# magnetorquer_extension_board_f1.net
KiCad netlist of a schematic drawn in EAGLE
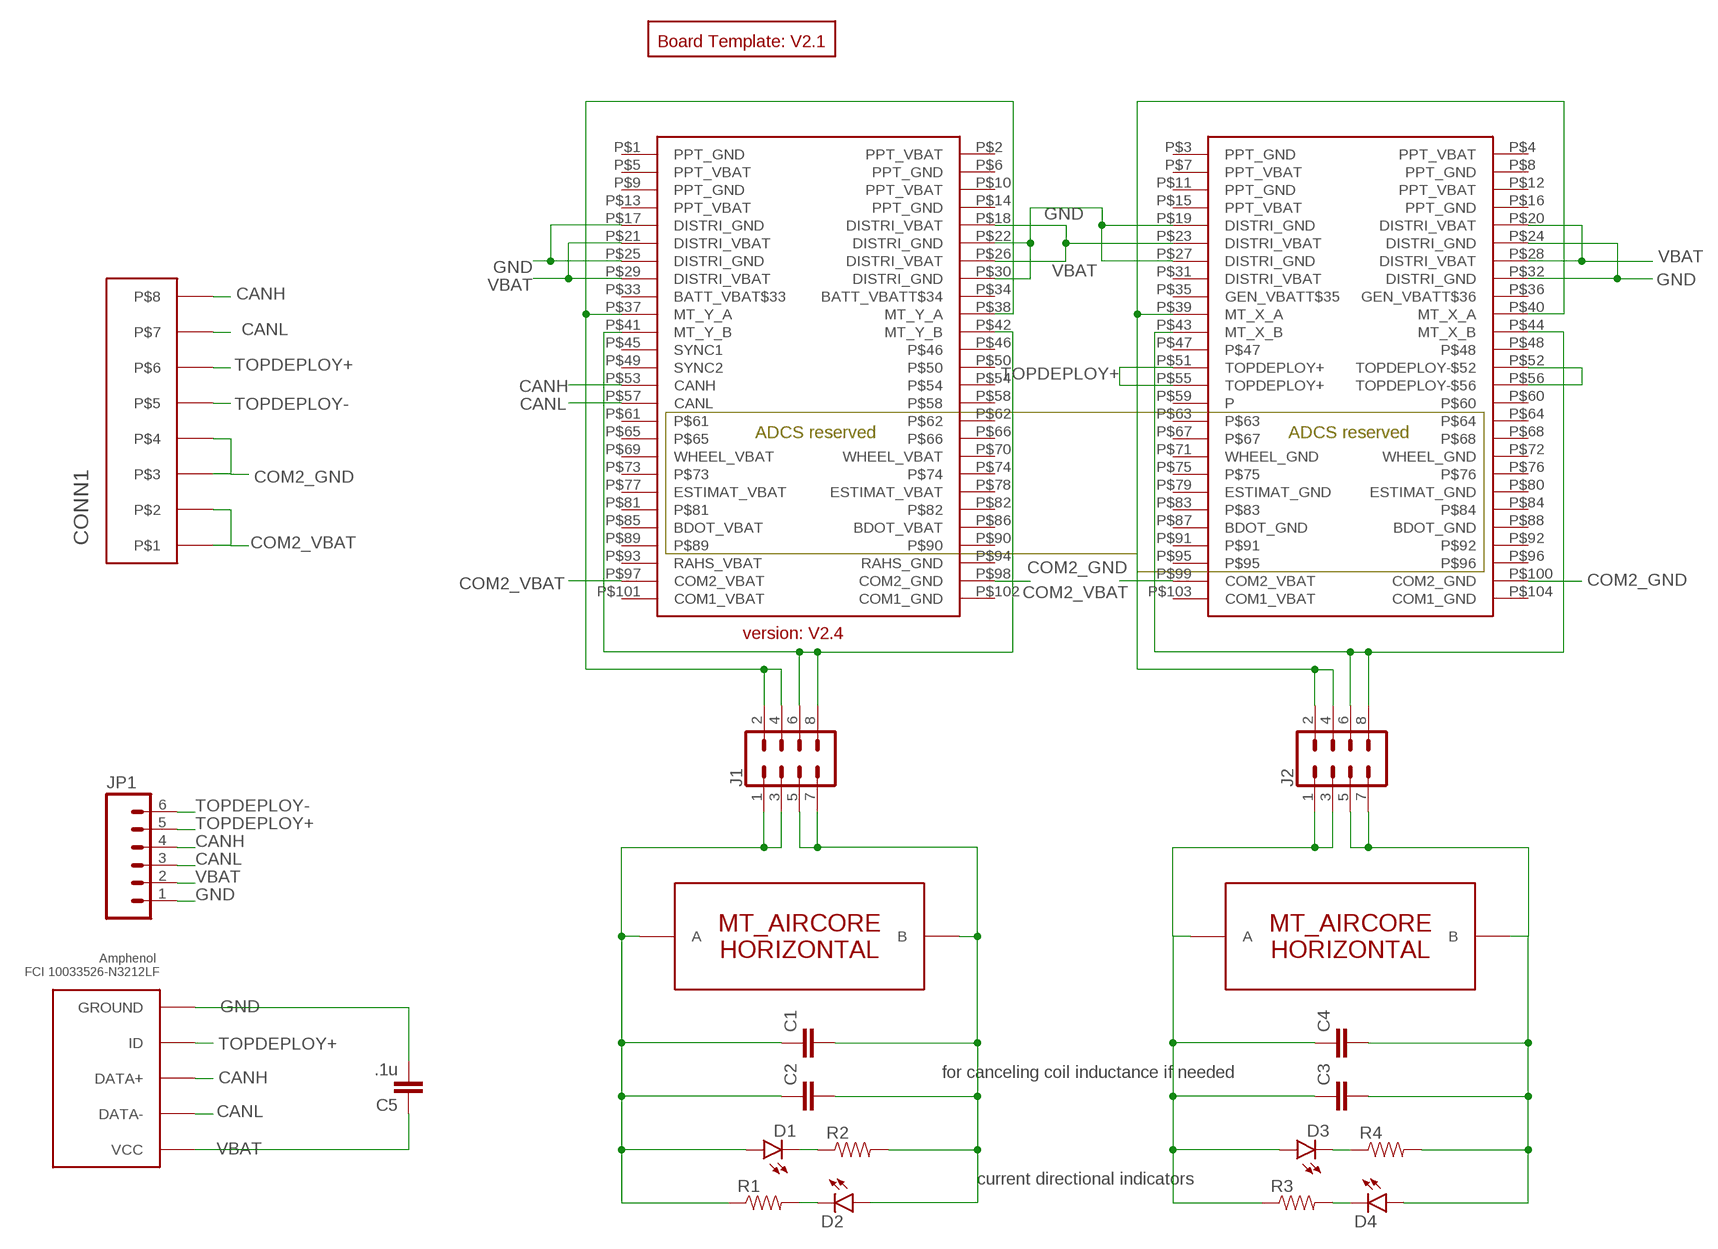
[diagram p0: schematic, sheet 1]

(export (version "E")
  (design (tool "Eeschema 10.0.6"))
  (components
    (comp (ref "C1")
      (value "CAPACITOR0805")
      (footprint "eagle-import:0805")
      (libsource (lib "eagle-import") (part "CAPACITOR0805"))
    )
    (comp (ref "C2")
      (value "CAPACITOR1210")
      (footprint "eagle-import:1210")
      (libsource (lib "eagle-import") (part "CAPACITOR1210"))
    )
    (comp (ref "C3")
      (value "CAPACITOR1210")
      (footprint "eagle-import:1210")
      (libsource (lib "eagle-import") (part "CAPACITOR1210"))
    )
    (comp (ref "C4")
      (value "CAPACITOR0805")
      (footprint "eagle-import:0805")
      (libsource (lib "eagle-import") (part "CAPACITOR0805"))
    )
    (comp (ref "C5")
      (value ".1u")
      (footprint "eagle-import:0805")
      (libsource (lib "eagle-import") (part "CAPACITOR0805"))
    )
    (comp (ref "CONN1")
      (value "PICOLOCK_8PICOLOCK_8")
      (footprint "eagle-import:PICOLOCK_8")
      (libsource (lib "eagle-import") (part "PICOLOCK_8PICOLOCK_8"))
    )
    (comp (ref "D1")
      (value "LED")
      (footprint "eagle-import:LED-1206")
      (libsource (lib "eagle-import") (part "LED"))
    )
    (comp (ref "D2")
      (value "LED")
      (footprint "eagle-import:LED-1206")
      (libsource (lib "eagle-import") (part "LED"))
    )
    (comp (ref "D3")
      (value "LED")
      (footprint "eagle-import:LED-1206")
      (libsource (lib "eagle-import") (part "LED"))
    )
    (comp (ref "D4")
      (value "LED")
      (footprint "eagle-import:LED-1206")
      (libsource (lib "eagle-import") (part "LED"))
    )
    (comp (ref "J1")
      (value "CONN_04X2")
      (footprint "eagle-import:2X4")
      (libsource (lib "eagle-import") (part "CONN_04X2"))
    )
    (comp (ref "J2")
      (value "CONN_04X2")
      (footprint "eagle-import:2X4")
      (libsource (lib "eagle-import") (part "CONN_04X2"))
    )
    (comp (ref "JP1")
      (value "M06LOCK")
      (footprint "eagle-import:1X06_LOCK")
      (libsource (lib "eagle-import") (part "M06LOCK"))
    )
    (comp (ref "MT_X")
      (value "MT_AIRCORE_HORIZONTAL")
      (footprint "eagle-import:MT_AIRCORE_HORIZONTAL")
      (libsource (lib "eagle-import") (part "MT_AIRCORE_HORIZONTAL"))
    )
    (comp (ref "MT_Y")
      (value "MT_AIRCORE_HORIZONTAL")
      (footprint "eagle-import:MT_AIRCORE_HORIZONTAL")
      (libsource (lib "eagle-import") (part "MT_AIRCORE_HORIZONTAL"))
    )
    (comp (ref "R1")
      (value "RESISTOR0805")
      (footprint "eagle-import:0805")
      (libsource (lib "eagle-import") (part "RESISTOR0805"))
    )
    (comp (ref "R2")
      (value "RESISTOR0805")
      (footprint "eagle-import:0805")
      (libsource (lib "eagle-import") (part "RESISTOR0805"))
    )
    (comp (ref "R3")
      (value "RESISTOR0805")
      (footprint "eagle-import:0805")
      (libsource (lib "eagle-import") (part "RESISTOR0805"))
    )
    (comp (ref "R4")
      (value "RESISTOR0805")
      (footprint "eagle-import:0805")
      (libsource (lib "eagle-import") (part "RESISTOR0805"))
    )
    (comp (ref "U$1")
      (value "PC104_CONNECTOR")
      (footprint "eagle-import:PC104_CONNECTOR")
      (libsource (lib "eagle-import") (part "PC104_CONNECTOR"))
    )
    (comp (ref "U$2")
      (value "BOARD_TEMPLATESERCURED")
      (footprint "eagle-import:BOARD_TEMPLATE_SECURED")
      (libsource (lib "eagle-import") (part "BOARD_TEMPLATESERCURED"))
    )
    (comp (ref "U$3")
      (value "USB_MINI-B_AMPHENOL")
      (footprint "eagle-import:USB_MINI_B")
      (libsource (lib "eagle-import") (part "USB_MINI-B_AMPHENOL"))
    )
  )
  (nets
    (net (code "1") (name "/CANH") (class "Default")
      (node (ref "CONN1") (pin "P$8") (pinfunction "P$8_P$8") (pintype "bidirectional"))
      (node (ref "JP1") (pin "4") (pinfunction "4_4") (pintype "passive"))
      (node (ref "U$1") (pin "P$53") (pinfunction "CANH_P$53") (pintype "bidirectional"))
      (node (ref "U$3") (pin "DATA+") (pinfunction "DATA+_DATA+") (pintype "bidirectional"))
    )
    (net (code "2") (name "/CANL") (class "Default")
      (node (ref "CONN1") (pin "P$7") (pinfunction "P$7_P$7") (pintype "bidirectional"))
      (node (ref "JP1") (pin "3") (pinfunction "3_3") (pintype "passive"))
      (node (ref "U$1") (pin "P$57") (pinfunction "CANL_P$57") (pintype "bidirectional"))
      (node (ref "U$3") (pin "DATA-") (pinfunction "DATA-_DATA-") (pintype "bidirectional"))
    )
    (net (code "3") (name "/COM2_GND") (class "Default")
      (node (ref "CONN1") (pin "P$3") (pinfunction "P$3_P$3") (pintype "bidirectional"))
      (node (ref "CONN1") (pin "P$4") (pinfunction "P$4_P$4") (pintype "bidirectional"))
      (node (ref "U$1") (pin "P$100") (pinfunction "COM2_GND_P$100") (pintype "bidirectional"))
      (node (ref "U$1") (pin "P$98") (pinfunction "COM2_GND_P$98") (pintype "bidirectional"))
    )
    (net (code "4") (name "/COM2_VBAT") (class "Default")
      (node (ref "CONN1") (pin "P$1") (pinfunction "P$1_P$1") (pintype "bidirectional"))
      (node (ref "CONN1") (pin "P$2") (pinfunction "P$2_P$2") (pintype "bidirectional"))
      (node (ref "U$1") (pin "P$97") (pinfunction "COM2_VBAT_P$97") (pintype "bidirectional"))
      (node (ref "U$1") (pin "P$99") (pinfunction "COM2_VBAT_P$99") (pintype "bidirectional"))
    )
    (net (code "5") (name "/GND") (class "Default")
      (node (ref "C5") (pin "2") (pinfunction "2_2") (pintype "passive"))
      (node (ref "JP1") (pin "1") (pinfunction "1_1") (pintype "passive"))
      (node (ref "U$1") (pin "P$17") (pinfunction "DISTRI_GND_P$17") (pintype "bidirectional"))
      (node (ref "U$1") (pin "P$19") (pinfunction "DISTRI_GND_P$19") (pintype "bidirectional"))
      (node (ref "U$1") (pin "P$22") (pinfunction "DISTRI_GND_P$22") (pintype "bidirectional"))
      (node (ref "U$1") (pin "P$24") (pinfunction "DISTRI_GND_P$24") (pintype "bidirectional"))
      (node (ref "U$1") (pin "P$25") (pinfunction "DISTRI_GND_P$25") (pintype "bidirectional"))
      (node (ref "U$1") (pin "P$27") (pinfunction "DISTRI_GND_P$27") (pintype "bidirectional"))
      (node (ref "U$1") (pin "P$30") (pinfunction "DISTRI_GND_P$30") (pintype "bidirectional"))
      (node (ref "U$1") (pin "P$32") (pinfunction "DISTRI_GND_P$32") (pintype "bidirectional"))
      (node (ref "U$3") (pin "GND1") (pinfunction "GROUND_GND1") (pintype "bidirectional"))
      (node (ref "U$3") (pin "GND2") (pinfunction "GROUND_GND2") (pintype "bidirectional"))
      (node (ref "U$3") (pin "GND3") (pinfunction "GROUND_GND3") (pintype "bidirectional"))
      (node (ref "U$3") (pin "GND4") (pinfunction "GROUND_GND4") (pintype "bidirectional"))
      (node (ref "U$3") (pin "GROUND") (pinfunction "GROUND_GROUND") (pintype "bidirectional"))
    )
    (net (code "6") (name "/TOPDEPLOY+") (class "Default")
      (node (ref "CONN1") (pin "P$6") (pinfunction "P$6_P$6") (pintype "bidirectional"))
      (node (ref "JP1") (pin "5") (pinfunction "5_5") (pintype "passive"))
      (node (ref "U$1") (pin "P$51") (pinfunction "TOPDEPLOY+_P$51") (pintype "bidirectional"))
      (node (ref "U$1") (pin "P$55") (pinfunction "TOPDEPLOY+_P$55") (pintype "bidirectional"))
      (node (ref "U$3") (pin "ID") (pinfunction "ID_ID") (pintype "bidirectional"))
    )
    (net (code "7") (name "/TOPDEPLOY-") (class "Default")
      (node (ref "CONN1") (pin "P$5") (pinfunction "P$5_P$5") (pintype "bidirectional"))
      (node (ref "JP1") (pin "6") (pinfunction "6_6") (pintype "passive"))
      (node (ref "U$1") (pin "P$52") (pinfunction "TOPDEPLOY-$52_P$52") (pintype "bidirectional"))
      (node (ref "U$1") (pin "P$56") (pinfunction "TOPDEPLOY-$56_P$56") (pintype "bidirectional"))
    )
    (net (code "8") (name "/VBAT") (class "Default")
      (node (ref "C5") (pin "1") (pinfunction "1_1") (pintype "passive"))
      (node (ref "JP1") (pin "2") (pinfunction "2_2") (pintype "passive"))
      (node (ref "U$1") (pin "P$18") (pinfunction "DISTRI_VBAT_P$18") (pintype "bidirectional"))
      (node (ref "U$1") (pin "P$20") (pinfunction "DISTRI_VBAT_P$20") (pintype "bidirectional"))
      (node (ref "U$1") (pin "P$21") (pinfunction "DISTRI_VBAT_P$21") (pintype "bidirectional"))
      (node (ref "U$1") (pin "P$23") (pinfunction "DISTRI_VBAT_P$23") (pintype "bidirectional"))
      (node (ref "U$1") (pin "P$26") (pinfunction "DISTRI_VBAT_P$26") (pintype "bidirectional"))
      (node (ref "U$1") (pin "P$28") (pinfunction "DISTRI_VBAT_P$28") (pintype "bidirectional"))
      (node (ref "U$1") (pin "P$29") (pinfunction "DISTRI_VBAT_P$29") (pintype "bidirectional"))
      (node (ref "U$3") (pin "VCC") (pinfunction "VCC_VCC") (pintype "bidirectional"))
    )
    (net (code "9") (name "Net-(C1-Pad1)") (class "Default")
      (node (ref "C1") (pin "1") (pinfunction "1_1") (pintype "passive"))
      (node (ref "C2") (pin "1") (pinfunction "1_1") (pintype "passive"))
      (node (ref "D1") (pin "A") (pinfunction "A_A") (pintype "passive"))
      (node (ref "J1") (pin "1") (pinfunction "1_1") (pintype "passive"))
      (node (ref "J1") (pin "3") (pinfunction "3_3") (pintype "passive"))
      (node (ref "MT_X") (pin "A") (pinfunction "A_A") (pintype "bidirectional"))
      (node (ref "R1") (pin "1") (pinfunction "1_1") (pintype "passive"))
    )
    (net (code "10") (name "Net-(C1-Pad2)") (class "Default")
      (node (ref "C1") (pin "2") (pinfunction "2_2") (pintype "passive"))
      (node (ref "C2") (pin "2") (pinfunction "2_2") (pintype "passive"))
      (node (ref "D2") (pin "A") (pinfunction "A_A") (pintype "passive"))
      (node (ref "J1") (pin "5") (pinfunction "5_5") (pintype "passive"))
      (node (ref "J1") (pin "7") (pinfunction "7_7") (pintype "passive"))
      (node (ref "MT_X") (pin "B") (pinfunction "B_B") (pintype "bidirectional"))
      (node (ref "R2") (pin "2") (pinfunction "2_2") (pintype "passive"))
    )
    (net (code "11") (name "Net-(C3-Pad1)") (class "Default")
      (node (ref "C3") (pin "1") (pinfunction "1_1") (pintype "passive"))
      (node (ref "C4") (pin "1") (pinfunction "1_1") (pintype "passive"))
      (node (ref "D3") (pin "A") (pinfunction "A_A") (pintype "passive"))
      (node (ref "J2") (pin "1") (pinfunction "1_1") (pintype "passive"))
      (node (ref "J2") (pin "3") (pinfunction "3_3") (pintype "passive"))
      (node (ref "MT_Y") (pin "A") (pinfunction "A_A") (pintype "bidirectional"))
      (node (ref "R3") (pin "1") (pinfunction "1_1") (pintype "passive"))
    )
    (net (code "12") (name "Net-(C3-Pad2)") (class "Default")
      (node (ref "C3") (pin "2") (pinfunction "2_2") (pintype "passive"))
      (node (ref "C4") (pin "2") (pinfunction "2_2") (pintype "passive"))
      (node (ref "D4") (pin "A") (pinfunction "A_A") (pintype "passive"))
      (node (ref "J2") (pin "5") (pinfunction "5_5") (pintype "passive"))
      (node (ref "J2") (pin "7") (pinfunction "7_7") (pintype "passive"))
      (node (ref "MT_Y") (pin "B") (pinfunction "B_B") (pintype "bidirectional"))
      (node (ref "R4") (pin "2") (pinfunction "2_2") (pintype "passive"))
    )
    (net (code "13") (name "Net-(D1-PadC)") (class "Default")
      (node (ref "D1") (pin "C") (pinfunction "C_C") (pintype "passive"))
      (node (ref "R2") (pin "1") (pinfunction "1_1") (pintype "passive"))
    )
    (net (code "14") (name "Net-(D2-PadC)") (class "Default")
      (node (ref "D2") (pin "C") (pinfunction "C_C") (pintype "passive"))
      (node (ref "R1") (pin "2") (pinfunction "2_2") (pintype "passive"))
    )
    (net (code "15") (name "Net-(D3-PadC)") (class "Default")
      (node (ref "D3") (pin "C") (pinfunction "C_C") (pintype "passive"))
      (node (ref "R4") (pin "1") (pinfunction "1_1") (pintype "passive"))
    )
    (net (code "16") (name "Net-(D4-PadC)") (class "Default")
      (node (ref "D4") (pin "C") (pinfunction "C_C") (pintype "passive"))
      (node (ref "R3") (pin "2") (pinfunction "2_2") (pintype "passive"))
    )
    (net (code "17") (name "Net-(J1-Pad2)") (class "Default")
      (node (ref "J1") (pin "2") (pinfunction "2_2") (pintype "passive"))
      (node (ref "J1") (pin "4") (pinfunction "4_4") (pintype "passive"))
      (node (ref "U$1") (pin "P$37") (pinfunction "MT_Y_A_P$37") (pintype "bidirectional"))
      (node (ref "U$1") (pin "P$38") (pinfunction "MT_Y_A_P$38") (pintype "bidirectional"))
    )
    (net (code "18") (name "Net-(J1-Pad6)") (class "Default")
      (node (ref "J1") (pin "6") (pinfunction "6_6") (pintype "passive"))
      (node (ref "J1") (pin "8") (pinfunction "8_8") (pintype "passive"))
      (node (ref "U$1") (pin "P$41") (pinfunction "MT_Y_B_P$41") (pintype "bidirectional"))
      (node (ref "U$1") (pin "P$42") (pinfunction "MT_Y_B_P$42") (pintype "bidirectional"))
    )
    (net (code "19") (name "Net-(J2-Pad2)") (class "Default")
      (node (ref "J2") (pin "2") (pinfunction "2_2") (pintype "passive"))
      (node (ref "J2") (pin "4") (pinfunction "4_4") (pintype "passive"))
      (node (ref "U$1") (pin "P$39") (pinfunction "MT_X_A_P$39") (pintype "bidirectional"))
      (node (ref "U$1") (pin "P$40") (pinfunction "MT_X_A_P$40") (pintype "bidirectional"))
    )
    (net (code "20") (name "Net-(J2-Pad6)") (class "Default")
      (node (ref "J2") (pin "6") (pinfunction "6_6") (pintype "passive"))
      (node (ref "J2") (pin "8") (pinfunction "8_8") (pintype "passive"))
      (node (ref "U$1") (pin "P$43") (pinfunction "MT_X_B_P$43") (pintype "bidirectional"))
      (node (ref "U$1") (pin "P$44") (pinfunction "MT_X_B_P$44") (pintype "bidirectional"))
    )
    (net (code "21") (name "unconnected-(U$1-BATT_VBAT$33-PadP$33)") (class "Default")
      (node (ref "U$1") (pin "P$33") (pinfunction "BATT_VBAT$33_P$33") (pintype "bidirectional"))
    )
    (net (code "22") (name "unconnected-(U$1-BATT_VBATT$34-PadP$34)") (class "Default")
      (node (ref "U$1") (pin "P$34") (pinfunction "BATT_VBATT$34_P$34") (pintype "bidirectional"))
    )
    (net (code "23") (name "unconnected-(U$1-BDOT_GND-PadP$87)") (class "Default")
      (node (ref "U$1") (pin "P$87") (pinfunction "BDOT_GND_P$87") (pintype "bidirectional"))
    )
    (net (code "24") (name "unconnected-(U$1-BDOT_GND-PadP$88)") (class "Default")
      (node (ref "U$1") (pin "P$88") (pinfunction "BDOT_GND_P$88") (pintype "bidirectional"))
    )
    (net (code "25") (name "unconnected-(U$1-BDOT_VBAT-PadP$85)") (class "Default")
      (node (ref "U$1") (pin "P$85") (pinfunction "BDOT_VBAT_P$85") (pintype "bidirectional"))
    )
    (net (code "26") (name "unconnected-(U$1-BDOT_VBAT-PadP$86)") (class "Default")
      (node (ref "U$1") (pin "P$86") (pinfunction "BDOT_VBAT_P$86") (pintype "bidirectional"))
    )
    (net (code "27") (name "unconnected-(U$1-COM1_GND-PadP$102)") (class "Default")
      (node (ref "U$1") (pin "P$102") (pinfunction "COM1_GND_P$102") (pintype "bidirectional"))
    )
    (net (code "28") (name "unconnected-(U$1-COM1_GND-PadP$104)") (class "Default")
      (node (ref "U$1") (pin "P$104") (pinfunction "COM1_GND_P$104") (pintype "bidirectional"))
    )
    (net (code "29") (name "unconnected-(U$1-COM1_VBAT-PadP$101)") (class "Default")
      (node (ref "U$1") (pin "P$101") (pinfunction "COM1_VBAT_P$101") (pintype "bidirectional"))
    )
    (net (code "30") (name "unconnected-(U$1-COM1_VBAT-PadP$103)") (class "Default")
      (node (ref "U$1") (pin "P$103") (pinfunction "COM1_VBAT_P$103") (pintype "bidirectional"))
    )
    (net (code "31") (name "unconnected-(U$1-DISTRI_VBAT-PadP$31)") (class "Default")
      (node (ref "U$1") (pin "P$31") (pinfunction "DISTRI_VBAT_P$31") (pintype "bidirectional"))
    )
    (net (code "32") (name "unconnected-(U$1-ESTIMAT_GND-PadP$79)") (class "Default")
      (node (ref "U$1") (pin "P$79") (pinfunction "ESTIMAT_GND_P$79") (pintype "bidirectional"))
    )
    (net (code "33") (name "unconnected-(U$1-ESTIMAT_GND-PadP$80)") (class "Default")
      (node (ref "U$1") (pin "P$80") (pinfunction "ESTIMAT_GND_P$80") (pintype "bidirectional"))
    )
    (net (code "34") (name "unconnected-(U$1-ESTIMAT_VBAT-PadP$77)") (class "Default")
      (node (ref "U$1") (pin "P$77") (pinfunction "ESTIMAT_VBAT_P$77") (pintype "bidirectional"))
    )
    (net (code "35") (name "unconnected-(U$1-ESTIMAT_VBAT-PadP$78)") (class "Default")
      (node (ref "U$1") (pin "P$78") (pinfunction "ESTIMAT_VBAT_P$78") (pintype "bidirectional"))
    )
    (net (code "36") (name "unconnected-(U$1-GEN_VBATT$35-PadP$35)") (class "Default")
      (node (ref "U$1") (pin "P$35") (pinfunction "GEN_VBATT$35_P$35") (pintype "bidirectional"))
    )
    (net (code "37") (name "unconnected-(U$1-GEN_VBATT$36-PadP$36)") (class "Default")
      (node (ref "U$1") (pin "P$36") (pinfunction "GEN_VBATT$36_P$36") (pintype "bidirectional"))
    )
    (net (code "38") (name "unconnected-(U$1-P-PadP$59)") (class "Default")
      (node (ref "U$1") (pin "P$59") (pinfunction "P_P$59") (pintype "bidirectional"))
    )
    (net (code "39") (name "unconnected-(U$1-PPT_GND-PadP$1)") (class "Default")
      (node (ref "U$1") (pin "P$1") (pinfunction "PPT_GND_P$1") (pintype "bidirectional"))
    )
    (net (code "40") (name "unconnected-(U$1-PPT_GND-PadP$3)") (class "Default")
      (node (ref "U$1") (pin "P$3") (pinfunction "PPT_GND_P$3") (pintype "bidirectional"))
    )
    (net (code "41") (name "unconnected-(U$1-PPT_GND-PadP$6)") (class "Default")
      (node (ref "U$1") (pin "P$6") (pinfunction "PPT_GND_P$6") (pintype "bidirectional"))
    )
    (net (code "42") (name "unconnected-(U$1-PPT_GND-PadP$8)") (class "Default")
      (node (ref "U$1") (pin "P$8") (pinfunction "PPT_GND_P$8") (pintype "bidirectional"))
    )
    (net (code "43") (name "unconnected-(U$1-PPT_GND-PadP$9)") (class "Default")
      (node (ref "U$1") (pin "P$9") (pinfunction "PPT_GND_P$9") (pintype "bidirectional"))
    )
    (net (code "44") (name "unconnected-(U$1-PPT_GND-PadP$11)") (class "Default")
      (node (ref "U$1") (pin "P$11") (pinfunction "PPT_GND_P$11") (pintype "bidirectional"))
    )
    (net (code "45") (name "unconnected-(U$1-PPT_GND-PadP$14)") (class "Default")
      (node (ref "U$1") (pin "P$14") (pinfunction "PPT_GND_P$14") (pintype "bidirectional"))
    )
    (net (code "46") (name "unconnected-(U$1-PPT_GND-PadP$16)") (class "Default")
      (node (ref "U$1") (pin "P$16") (pinfunction "PPT_GND_P$16") (pintype "bidirectional"))
    )
    (net (code "47") (name "unconnected-(U$1-PPT_VBAT-PadP$2)") (class "Default")
      (node (ref "U$1") (pin "P$2") (pinfunction "PPT_VBAT_P$2") (pintype "bidirectional"))
    )
    (net (code "48") (name "unconnected-(U$1-PPT_VBAT-PadP$4)") (class "Default")
      (node (ref "U$1") (pin "P$4") (pinfunction "PPT_VBAT_P$4") (pintype "bidirectional"))
    )
    (net (code "49") (name "unconnected-(U$1-PPT_VBAT-PadP$5)") (class "Default")
      (node (ref "U$1") (pin "P$5") (pinfunction "PPT_VBAT_P$5") (pintype "bidirectional"))
    )
    (net (code "50") (name "unconnected-(U$1-PPT_VBAT-PadP$7)") (class "Default")
      (node (ref "U$1") (pin "P$7") (pinfunction "PPT_VBAT_P$7") (pintype "bidirectional"))
    )
    (net (code "51") (name "unconnected-(U$1-PPT_VBAT-PadP$10)") (class "Default")
      (node (ref "U$1") (pin "P$10") (pinfunction "PPT_VBAT_P$10") (pintype "bidirectional"))
    )
    (net (code "52") (name "unconnected-(U$1-PPT_VBAT-PadP$12)") (class "Default")
      (node (ref "U$1") (pin "P$12") (pinfunction "PPT_VBAT_P$12") (pintype "bidirectional"))
    )
    (net (code "53") (name "unconnected-(U$1-PPT_VBAT-PadP$13)") (class "Default")
      (node (ref "U$1") (pin "P$13") (pinfunction "PPT_VBAT_P$13") (pintype "bidirectional"))
    )
    (net (code "54") (name "unconnected-(U$1-PPT_VBAT-PadP$15)") (class "Default")
      (node (ref "U$1") (pin "P$15") (pinfunction "PPT_VBAT_P$15") (pintype "bidirectional"))
    )
    (net (code "55") (name "unconnected-(U$1-PadP$46)") (class "Default")
      (node (ref "U$1") (pin "P$46") (pinfunction "P$46_P$46") (pintype "bidirectional"))
    )
    (net (code "56") (name "unconnected-(U$1-PadP$47)") (class "Default")
      (node (ref "U$1") (pin "P$47") (pinfunction "P$47_P$47") (pintype "bidirectional"))
    )
    (net (code "57") (name "unconnected-(U$1-PadP$48)") (class "Default")
      (node (ref "U$1") (pin "P$48") (pinfunction "P$48_P$48") (pintype "bidirectional"))
    )
    (net (code "58") (name "unconnected-(U$1-PadP$50)") (class "Default")
      (node (ref "U$1") (pin "P$50") (pinfunction "P$50_P$50") (pintype "bidirectional"))
    )
    (net (code "59") (name "unconnected-(U$1-PadP$54)") (class "Default")
      (node (ref "U$1") (pin "P$54") (pinfunction "P$54_P$54") (pintype "bidirectional"))
    )
    (net (code "60") (name "unconnected-(U$1-PadP$58)") (class "Default")
      (node (ref "U$1") (pin "P$58") (pinfunction "P$58_P$58") (pintype "bidirectional"))
    )
    (net (code "61") (name "unconnected-(U$1-PadP$60)") (class "Default")
      (node (ref "U$1") (pin "P$60") (pinfunction "P$60_P$60") (pintype "bidirectional"))
    )
    (net (code "62") (name "unconnected-(U$1-PadP$61)") (class "Default")
      (node (ref "U$1") (pin "P$61") (pinfunction "P$61_P$61") (pintype "bidirectional"))
    )
    (net (code "63") (name "unconnected-(U$1-PadP$62)") (class "Default")
      (node (ref "U$1") (pin "P$62") (pinfunction "P$62_P$62") (pintype "bidirectional"))
    )
    (net (code "64") (name "unconnected-(U$1-PadP$63)") (class "Default")
      (node (ref "U$1") (pin "P$63") (pinfunction "P$63_P$63") (pintype "bidirectional"))
    )
    (net (code "65") (name "unconnected-(U$1-PadP$64)") (class "Default")
      (node (ref "U$1") (pin "P$64") (pinfunction "P$64_P$64") (pintype "bidirectional"))
    )
    (net (code "66") (name "unconnected-(U$1-PadP$65)") (class "Default")
      (node (ref "U$1") (pin "P$65") (pinfunction "P$65_P$65") (pintype "bidirectional"))
    )
    (net (code "67") (name "unconnected-(U$1-PadP$66)") (class "Default")
      (node (ref "U$1") (pin "P$66") (pinfunction "P$66_P$66") (pintype "bidirectional"))
    )
    (net (code "68") (name "unconnected-(U$1-PadP$67)") (class "Default")
      (node (ref "U$1") (pin "P$67") (pinfunction "P$67_P$67") (pintype "bidirectional"))
    )
    (net (code "69") (name "unconnected-(U$1-PadP$68)") (class "Default")
      (node (ref "U$1") (pin "P$68") (pinfunction "P$68_P$68") (pintype "bidirectional"))
    )
    (net (code "70") (name "unconnected-(U$1-PadP$73)") (class "Default")
      (node (ref "U$1") (pin "P$73") (pinfunction "P$73_P$73") (pintype "bidirectional"))
    )
    (net (code "71") (name "unconnected-(U$1-PadP$74)") (class "Default")
      (node (ref "U$1") (pin "P$74") (pinfunction "P$74_P$74") (pintype "bidirectional"))
    )
    (net (code "72") (name "unconnected-(U$1-PadP$75)") (class "Default")
      (node (ref "U$1") (pin "P$75") (pinfunction "P$75_P$75") (pintype "bidirectional"))
    )
    (net (code "73") (name "unconnected-(U$1-PadP$76)") (class "Default")
      (node (ref "U$1") (pin "P$76") (pinfunction "P$76_P$76") (pintype "bidirectional"))
    )
    (net (code "74") (name "unconnected-(U$1-PadP$81)") (class "Default")
      (node (ref "U$1") (pin "P$81") (pinfunction "P$81_P$81") (pintype "bidirectional"))
    )
    (net (code "75") (name "unconnected-(U$1-PadP$82)") (class "Default")
      (node (ref "U$1") (pin "P$82") (pinfunction "P$82_P$82") (pintype "bidirectional"))
    )
    (net (code "76") (name "unconnected-(U$1-PadP$83)") (class "Default")
      (node (ref "U$1") (pin "P$83") (pinfunction "P$83_P$83") (pintype "bidirectional"))
    )
    (net (code "77") (name "unconnected-(U$1-PadP$84)") (class "Default")
      (node (ref "U$1") (pin "P$84") (pinfunction "P$84_P$84") (pintype "bidirectional"))
    )
    (net (code "78") (name "unconnected-(U$1-PadP$89)") (class "Default")
      (node (ref "U$1") (pin "P$89") (pinfunction "P$89_P$89") (pintype "bidirectional"))
    )
    (net (code "79") (name "unconnected-(U$1-PadP$90)") (class "Default")
      (node (ref "U$1") (pin "P$90") (pinfunction "P$90_P$90") (pintype "bidirectional"))
    )
    (net (code "80") (name "unconnected-(U$1-PadP$91)") (class "Default")
      (node (ref "U$1") (pin "P$91") (pinfunction "P$91_P$91") (pintype "bidirectional"))
    )
    (net (code "81") (name "unconnected-(U$1-PadP$92)") (class "Default")
      (node (ref "U$1") (pin "P$92") (pinfunction "P$92_P$92") (pintype "bidirectional"))
    )
    (net (code "82") (name "unconnected-(U$1-PadP$95)") (class "Default")
      (node (ref "U$1") (pin "P$95") (pinfunction "P$95_P$95") (pintype "bidirectional"))
    )
    (net (code "83") (name "unconnected-(U$1-PadP$96)") (class "Default")
      (node (ref "U$1") (pin "P$96") (pinfunction "P$96_P$96") (pintype "bidirectional"))
    )
    (net (code "84") (name "unconnected-(U$1-RAHS_GND-PadP$94)") (class "Default")
      (node (ref "U$1") (pin "P$94") (pinfunction "RAHS_GND_P$94") (pintype "bidirectional"))
    )
    (net (code "85") (name "unconnected-(U$1-RAHS_VBAT-PadP$93)") (class "Default")
      (node (ref "U$1") (pin "P$93") (pinfunction "RAHS_VBAT_P$93") (pintype "bidirectional"))
    )
    (net (code "86") (name "unconnected-(U$1-SYNC1-PadP$45)") (class "Default")
      (node (ref "U$1") (pin "P$45") (pinfunction "SYNC1_P$45") (pintype "bidirectional"))
    )
    (net (code "87") (name "unconnected-(U$1-SYNC2-PadP$49)") (class "Default")
      (node (ref "U$1") (pin "P$49") (pinfunction "SYNC2_P$49") (pintype "bidirectional"))
    )
    (net (code "88") (name "unconnected-(U$1-WHEEL_GND-PadP$71)") (class "Default")
      (node (ref "U$1") (pin "P$71") (pinfunction "WHEEL_GND_P$71") (pintype "bidirectional"))
    )
    (net (code "89") (name "unconnected-(U$1-WHEEL_GND-PadP$72)") (class "Default")
      (node (ref "U$1") (pin "P$72") (pinfunction "WHEEL_GND_P$72") (pintype "bidirectional"))
    )
    (net (code "90") (name "unconnected-(U$1-WHEEL_VBAT-PadP$69)") (class "Default")
      (node (ref "U$1") (pin "P$69") (pinfunction "WHEEL_VBAT_P$69") (pintype "bidirectional"))
    )
    (net (code "91") (name "unconnected-(U$1-WHEEL_VBAT-PadP$70)") (class "Default")
      (node (ref "U$1") (pin "P$70") (pinfunction "WHEEL_VBAT_P$70") (pintype "bidirectional"))
    )
  )
)
